# powerblade1430_1v0.net
KiCad netlist of a schematic drawn in EAGLE
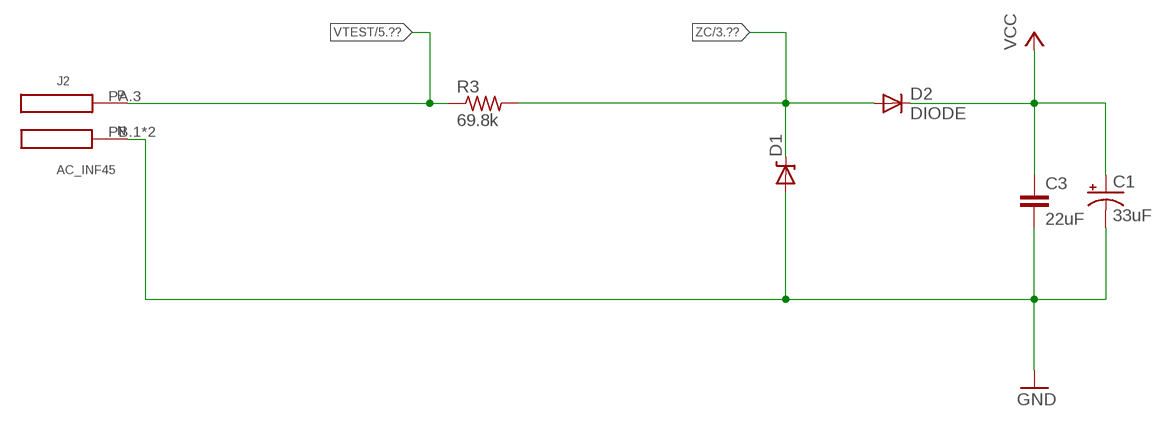
[diagram p0: schematic, sheet 1]
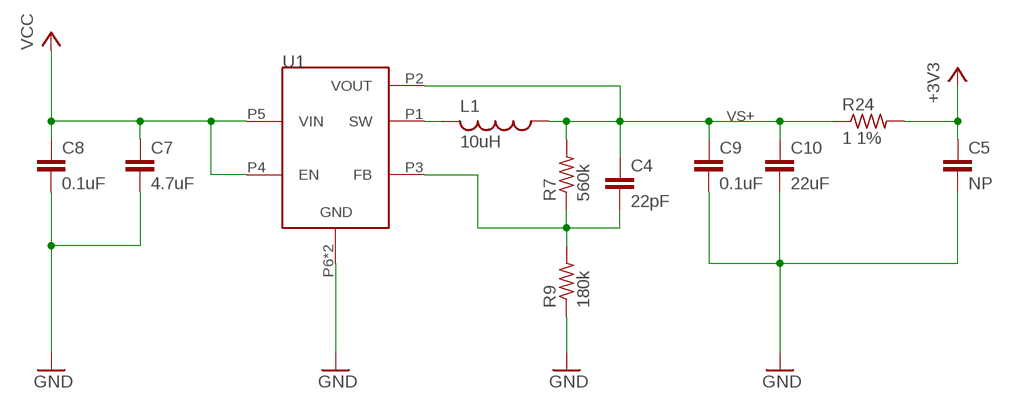
[diagram p1: schematic, sheet 2]
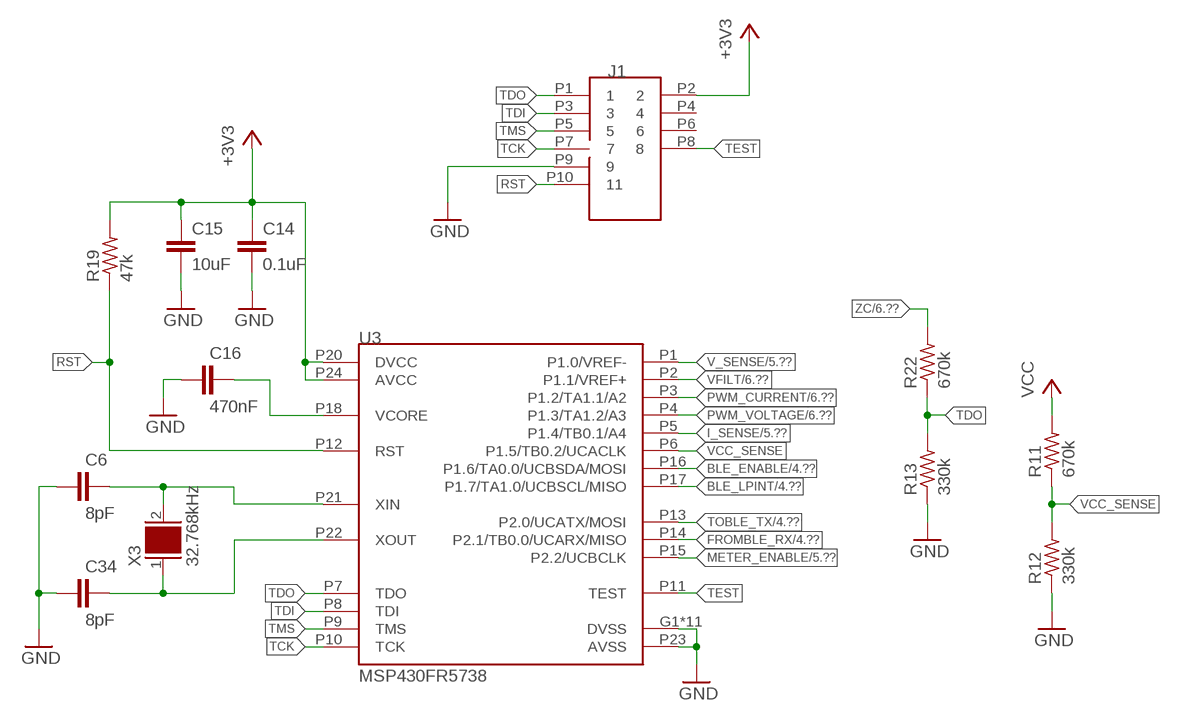
[diagram p2: schematic, sheet 3]
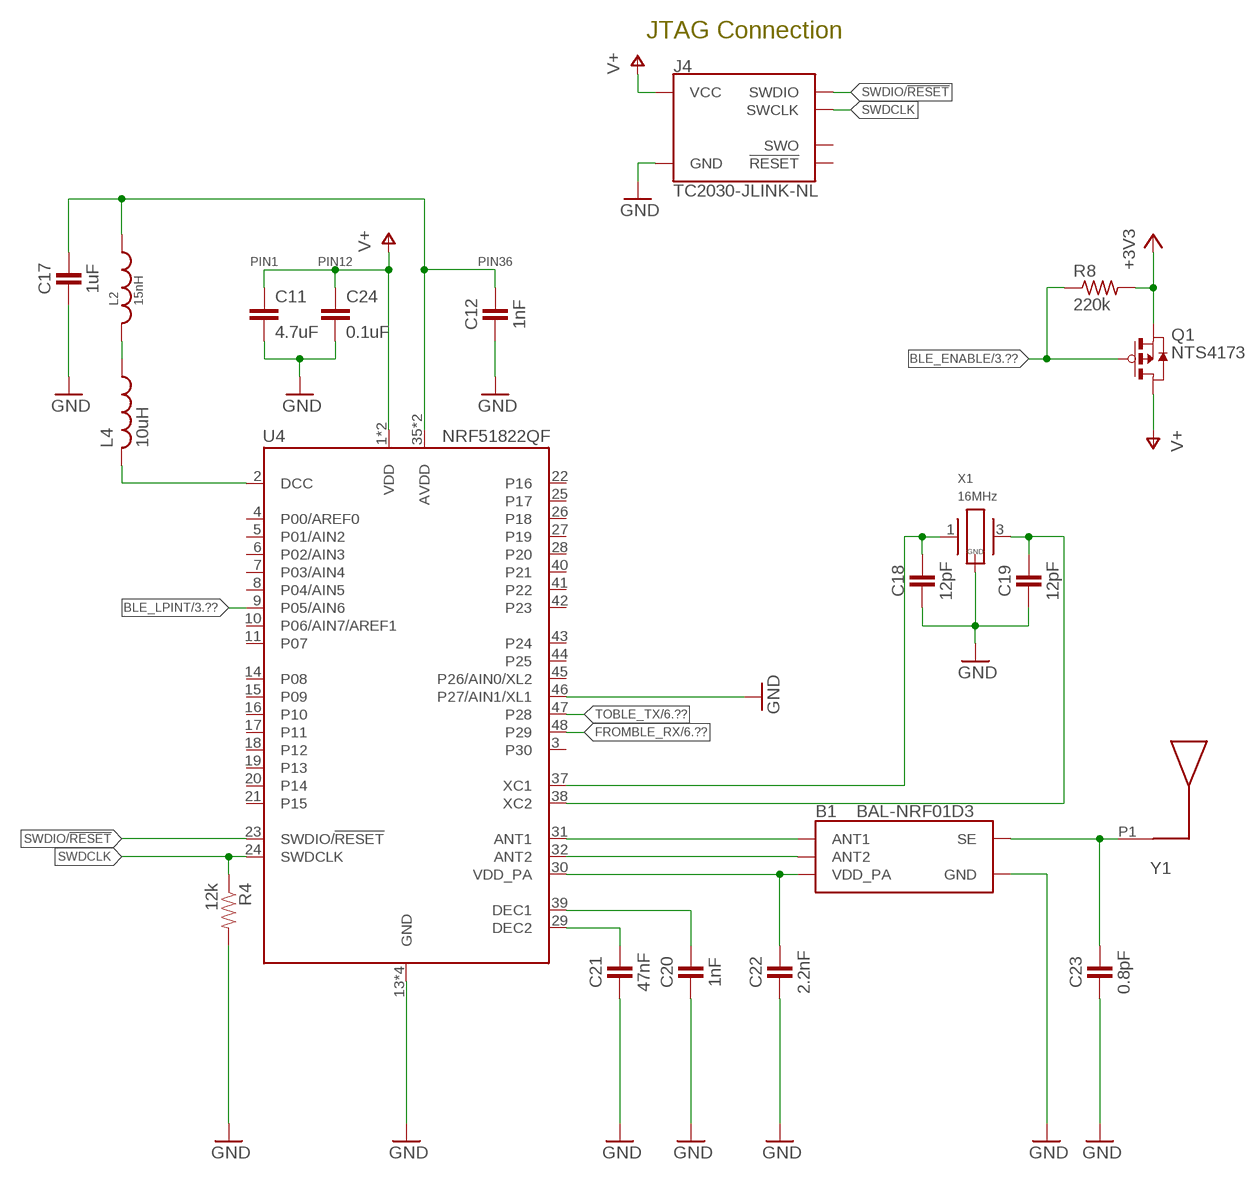
[diagram p3: schematic, sheet 4]
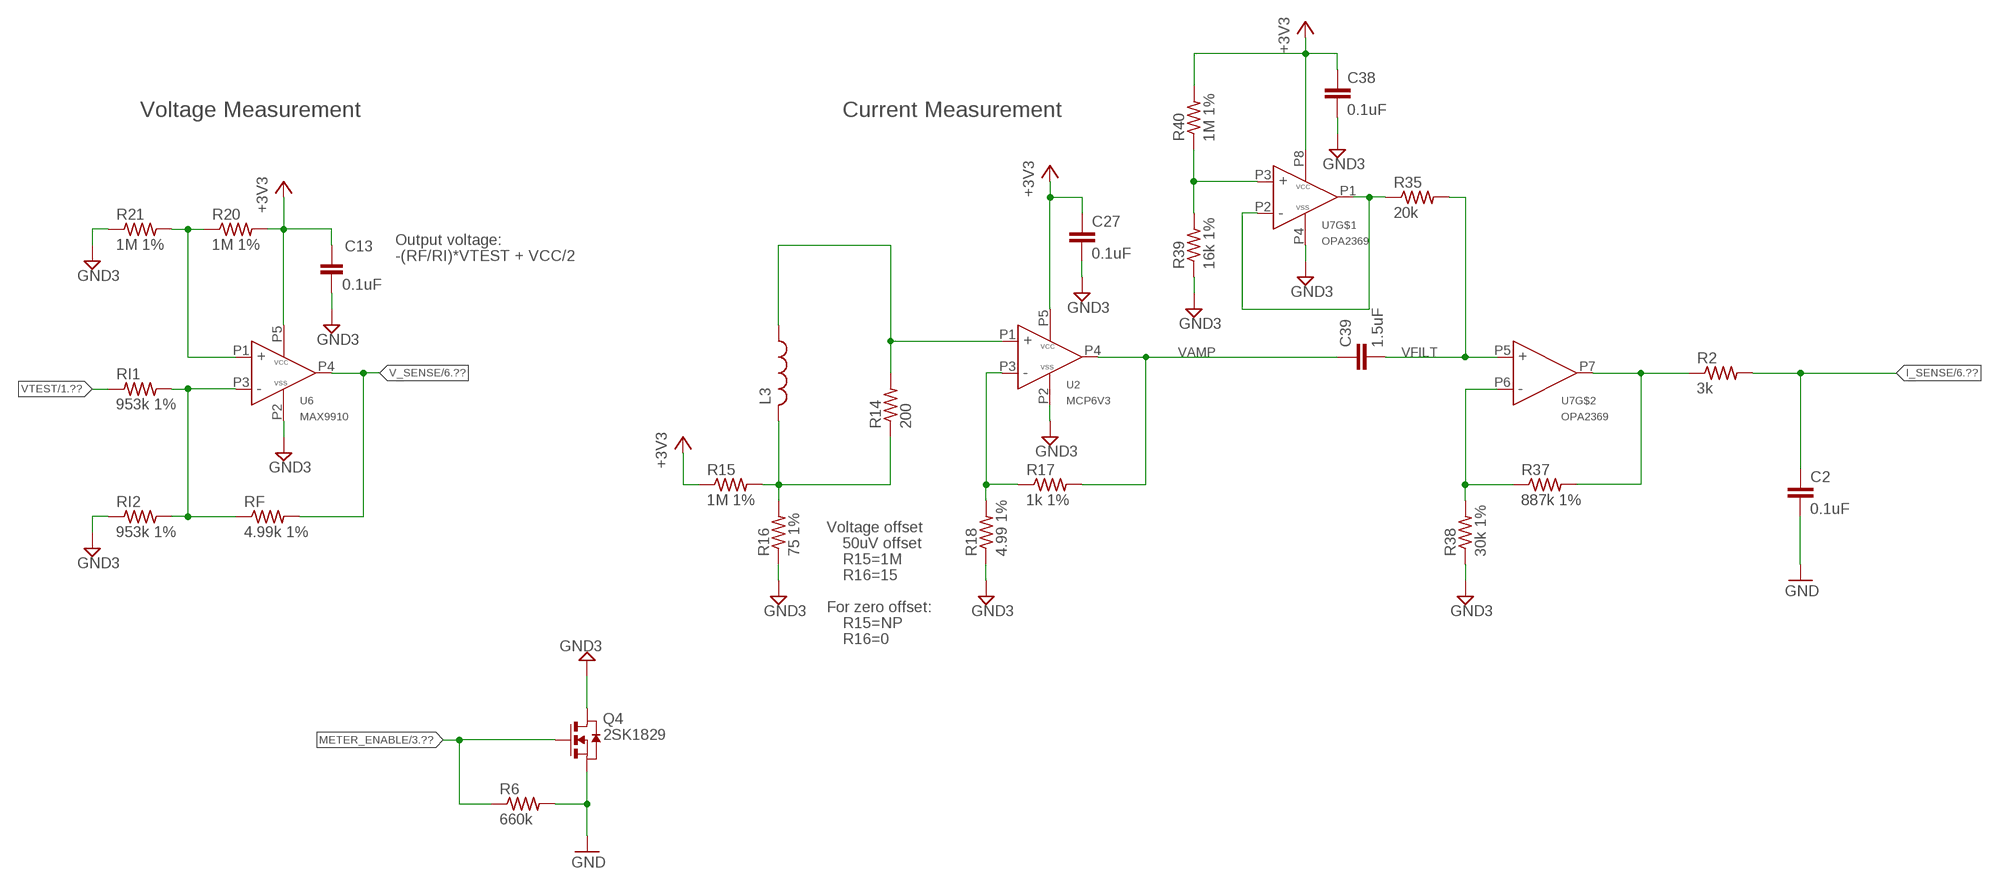
[diagram p4: schematic, sheet 5]
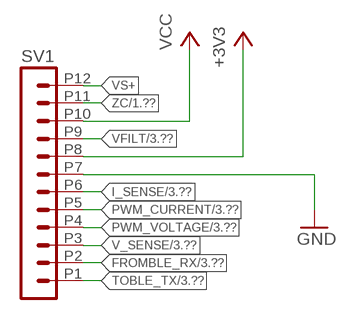
[diagram p5: schematic, sheet 6]

(export (version "E")
  (design (tool "Eeschema 10.0.6"))
  (components
    (comp (ref "SV1")
      (value "MA12-11M27")
      (footprint "eagle-import:MA12-1_1MM27")
      (libsource (lib "eagle-import") (part "MA12-11M27"))
    )
    (comp (ref "B1")
      (value "BAL-NRF01D3")
      (footprint "eagle-import:BAL-NRF01D3")
      (libsource (lib "eagle-import") (part "BAL-NRF01D3"))
    )
    (comp (ref "C11")
      (value "4.7uF")
      (footprint "eagle-import:C0402")
      (libsource (lib "eagle-import") (part "C-EUC0402"))
    )
    (comp (ref "C12")
      (value "1nF")
      (footprint "eagle-import:0402_CAP")
      (libsource (lib "eagle-import") (part "CAPACITOR"))
    )
    (comp (ref "C17")
      (value "1uF")
      (footprint "eagle-import:0402_CAP")
      (libsource (lib "eagle-import") (part "CAPACITOR"))
    )
    (comp (ref "C18")
      (value "12pF")
      (footprint "eagle-import:0402_CAP")
      (libsource (lib "eagle-import") (part "CAPACITOR"))
    )
    (comp (ref "C19")
      (value "12pF")
      (footprint "eagle-import:0402_CAP")
      (libsource (lib "eagle-import") (part "CAPACITOR"))
    )
    (comp (ref "C20")
      (value "1nF")
      (footprint "eagle-import:0402_CAP")
      (libsource (lib "eagle-import") (part "CAPACITOR"))
    )
    (comp (ref "C21")
      (value "47nF")
      (footprint "eagle-import:0402_CAP")
      (libsource (lib "eagle-import") (part "CAPACITOR"))
    )
    (comp (ref "C22")
      (value "2.2nF")
      (footprint "eagle-import:0402_CAP")
      (libsource (lib "eagle-import") (part "CAPACITOR"))
    )
    (comp (ref "C23")
      (value "0.8pF")
      (footprint "eagle-import:0402_CAP")
      (libsource (lib "eagle-import") (part "CAPACITOR"))
    )
    (comp (ref "C24")
      (value "0.1uF")
      (footprint "eagle-import:C0402")
      (libsource (lib "eagle-import") (part "C-EUC0402"))
    )
    (comp (ref "J4")
      (value "TC2030-JLINK-NL")
      (footprint "eagle-import:TC2030-IDC-NL")
      (libsource (lib "eagle-import") (part "TC2030-JLINK-NL"))
    )
    (comp (ref "L2")
      (value "15nH")
      (footprint "eagle-import:0402_CAP")
      (libsource (lib "eagle-import") (part "INDUCTOR0402"))
    )
    (comp (ref "L4")
      (value "10uH")
      (footprint "eagle-import:C0603_TN")
      (libsource (lib "eagle-import") (part "L-USL0603_TN"))
    )
    (comp (ref "Q1")
      (value "NTS4173")
      (footprint "eagle-import:SC-70-3")
      (libsource (lib "eagle-import") (part "NTS4173"))
    )
    (comp (ref "R4")
      (value "12k")
      (footprint "eagle-import:0402_RES")
      (libsource (lib "eagle-import") (part "RESISTOR"))
    )
    (comp (ref "R8")
      (value "220k")
      (footprint "eagle-import:R0402_SM")
      (libsource (lib "eagle-import") (part "R-US_R0402_SM"))
    )
    (comp (ref "U4")
      (value "NRF51822QF")
      (footprint "eagle-import:QFN-48-6MM")
      (libsource (lib "eagle-import") (part "NRF51822QF"))
    )
    (comp (ref "X1")
      (value "16MHz")
      (footprint "eagle-import:TXC-8Y")
      (libsource (lib "eagle-import") (part "TXC-8Y"))
    )
    (comp (ref "Y1")
      (value "UREACH_XTEND")
      (footprint "eagle-import:UREACH_XTEND")
      (libsource (lib "eagle-import") (part "UREACH_XTEND"))
    )
    (comp (ref "C6")
      (value "8pF")
      (footprint "eagle-import:C0402")
      (libsource (lib "eagle-import") (part "C-EUC0402"))
    )
    (comp (ref "C14")
      (value "0.1uF")
      (footprint "eagle-import:C0402")
      (libsource (lib "eagle-import") (part "C-EUC0402"))
    )
    (comp (ref "C15")
      (value "10uF")
      (footprint "eagle-import:C0603_SM")
      (libsource (lib "eagle-import") (part "C-EUC0603_SM"))
    )
    (comp (ref "C16")
      (value "470nF")
      (footprint "eagle-import:C0402")
      (libsource (lib "eagle-import") (part "C-EUC0402"))
    )
    (comp (ref "C34")
      (value "8pF")
      (footprint "eagle-import:C0402")
      (libsource (lib "eagle-import") (part "C-EUC0402"))
    )
    (comp (ref "J1")
      (value "JTAG_14PIN_IDC-ND")
      (footprint "eagle-import:TC2050-IDC-NL-430-ND")
      (libsource (lib "eagle-import") (part "JTAG_14PIN_IDC-ND"))
    )
    (comp (ref "R11")
      (value "670k")
      (footprint "eagle-import:R0402")
      (libsource (lib "eagle-import") (part "R-US_R0402"))
    )
    (comp (ref "R12")
      (value "330k")
      (footprint "eagle-import:R0402")
      (libsource (lib "eagle-import") (part "R-US_R0402"))
    )
    (comp (ref "R13")
      (value "330k")
      (footprint "eagle-import:R0402")
      (libsource (lib "eagle-import") (part "R-US_R0402"))
    )
    (comp (ref "R19")
      (value "47k")
      (footprint "eagle-import:R0402")
      (libsource (lib "eagle-import") (part "R-US_R0402"))
    )
    (comp (ref "R22")
      (value "670k")
      (footprint "eagle-import:R0402")
      (libsource (lib "eagle-import") (part "R-US_R0402"))
    )
    (comp (ref "U3")
      (value "MSP430FR5738")
      (footprint "eagle-import:VQFN-24")
      (libsource (lib "eagle-import") (part "MSP430FR5738"))
    )
    (comp (ref "X3")
      (value "32.768kHz")
      (footprint "eagle-import:0805")
      (libsource (lib "eagle-import") (part "CRYSTAL_0805"))
    )
    (comp (ref "C2")
      (value "0.1uF")
      (footprint "eagle-import:C0402")
      (libsource (lib "eagle-import") (part "C-EUC0402"))
    )
    (comp (ref "C13")
      (value "0.1uF")
      (footprint "eagle-import:0402_CAP")
      (libsource (lib "eagle-import") (part "CAPACITOR"))
    )
    (comp (ref "C27")
      (value "0.1uF")
      (footprint "eagle-import:C0402")
      (libsource (lib "eagle-import") (part "C-EUC0402"))
    )
    (comp (ref "C38")
      (value "0.1uF")
      (footprint "eagle-import:C0402")
      (libsource (lib "eagle-import") (part "C-EUC0402"))
    )
    (comp (ref "C39")
      (value "1.5uF")
      (footprint "eagle-import:C0402")
      (libsource (lib "eagle-import") (part "C-EUC0402"))
    )
    (comp (ref "L3")
      (value "L-USL0805")
      (footprint "eagle-import:L0805")
      (libsource (lib "eagle-import") (part "L-USL0805"))
    )
    (comp (ref "Q4")
      (value "2SK1829")
      (footprint "eagle-import:SC-70-3")
      (libsource (lib "eagle-import") (part "2SK1829"))
    )
    (comp (ref "R2")
      (value "3k")
      (footprint "eagle-import:R0402_SM")
      (libsource (lib "eagle-import") (part "R-US_R0402_SM"))
    )
    (comp (ref "R6")
      (value "660k")
      (footprint "eagle-import:R0402")
      (libsource (lib "eagle-import") (part "R-US_R0402"))
    )
    (comp (ref "R14")
      (value "200")
      (footprint "eagle-import:R0402")
      (libsource (lib "eagle-import") (part "R-US_R0402"))
    )
    (comp (ref "R15")
      (value "1M 1%")
      (footprint "eagle-import:R0402")
      (libsource (lib "eagle-import") (part "R-US_R0402"))
    )
    (comp (ref "R16")
      (value "75 1%")
      (footprint "eagle-import:R0402")
      (libsource (lib "eagle-import") (part "R-US_R0402"))
    )
    (comp (ref "R17")
      (value "1k 1%")
      (footprint "eagle-import:R0402")
      (libsource (lib "eagle-import") (part "R-US_R0402"))
    )
    (comp (ref "R18")
      (value "4.99 1%")
      (footprint "eagle-import:R0402")
      (libsource (lib "eagle-import") (part "R-US_R0402"))
    )
    (comp (ref "R20")
      (value "1M 1%")
      (footprint "eagle-import:R0402")
      (libsource (lib "eagle-import") (part "R-US_R0402"))
    )
    (comp (ref "R21")
      (value "1M 1%")
      (footprint "eagle-import:R0402_SM")
      (libsource (lib "eagle-import") (part "R-US_R0402_SM"))
    )
    (comp (ref "R35")
      (value "20k")
      (footprint "eagle-import:R0402")
      (libsource (lib "eagle-import") (part "R-US_R0402"))
    )
    (comp (ref "R37")
      (value "887k 1%")
      (footprint "eagle-import:R0402")
      (libsource (lib "eagle-import") (part "R-US_R0402"))
    )
    (comp (ref "R38")
      (value "30k 1%")
      (footprint "eagle-import:R0402")
      (libsource (lib "eagle-import") (part "R-US_R0402"))
    )
    (comp (ref "R39")
      (value "16k 1%")
      (footprint "eagle-import:R0402")
      (libsource (lib "eagle-import") (part "R-US_R0402"))
    )
    (comp (ref "R40")
      (value "1M 1%")
      (footprint "eagle-import:R0402")
      (libsource (lib "eagle-import") (part "R-US_R0402"))
    )
    (comp (ref "RF")
      (value "4.99k 1%")
      (footprint "eagle-import:R0402")
      (libsource (lib "eagle-import") (part "R-US_R0402"))
    )
    (comp (ref "RI1")
      (value "953k 1%")
      (footprint "eagle-import:R0402")
      (libsource (lib "eagle-import") (part "R-US_R0402"))
    )
    (comp (ref "RI2")
      (value "953k 1%")
      (footprint "eagle-import:R0402")
      (libsource (lib "eagle-import") (part "R-US_R0402"))
    )
    (comp (ref "U2")
      (value "MCP6V3")
      (footprint "eagle-import:SC70-5")
      (fields (field (name "DIGIKEY") "296-19547-1-ND"))
      (libsource (lib "eagle-import") (part "MCP6V3"))
    )
    (comp (ref "U6")
      (value "MAX9910")
      (footprint "eagle-import:SC70-5")
      (fields (field (name "DIGIKEY") "296-25252-1-ND"))
      (libsource (lib "eagle-import") (part "MAX9910"))
    )
    (comp (ref "U7")
      (value "OPA2369")
      (footprint "eagle-import:SOT-23-8")
      (libsource (lib "eagle-import") (part "OPA2369"))
    )
    (comp (ref "C4")
      (value "22pF")
      (footprint "eagle-import:C0402")
      (libsource (lib "eagle-import") (part "C-EUC0402"))
    )
    (comp (ref "C5")
      (value "NP")
      (footprint "eagle-import:C0603_TN")
      (libsource (lib "eagle-import") (part "C-EUC0603_TN"))
    )
    (comp (ref "C7")
      (value "4.7uF")
      (footprint "eagle-import:C0402")
      (libsource (lib "eagle-import") (part "C-EUC0402"))
    )
    (comp (ref "C8")
      (value "0.1uF")
      (footprint "eagle-import:C0402")
      (libsource (lib "eagle-import") (part "C-EUC0402"))
    )
    (comp (ref "C9")
      (value "0.1uF")
      (footprint "eagle-import:C0402_SM")
      (libsource (lib "eagle-import") (part "C-EUC0402_SM"))
    )
    (comp (ref "C10")
      (value "22uF")
      (footprint "eagle-import:C0603_SM")
      (libsource (lib "eagle-import") (part "C-EUC0603_SM"))
    )
    (comp (ref "L1")
      (value "10uH")
      (footprint "eagle-import:L0805")
      (libsource (lib "eagle-import") (part "L-USL0805"))
    )
    (comp (ref "R7")
      (value "560k")
      (footprint "eagle-import:R0402")
      (libsource (lib "eagle-import") (part "R-US_R0402"))
    )
    (comp (ref "R9")
      (value "180k")
      (footprint "eagle-import:R0402")
      (libsource (lib "eagle-import") (part "R-US_R0402"))
    )
    (comp (ref "R24")
      (value "1 1%")
      (footprint "eagle-import:R0603_SM")
      (libsource (lib "eagle-import") (part "R-US_R0603_SM"))
    )
    (comp (ref "U1")
      (value "TPS62122")
      (footprint "eagle-import:WDFN-6")
      (libsource (lib "eagle-import") (part "TPS62122"))
    )
    (comp (ref "C1")
      (value "33uF")
      (footprint "eagle-import:CPOL0805_SM")
      (libsource (lib "eagle-import") (part "CPOL-US0805_SM"))
    )
    (comp (ref "C3")
      (value "22uF")
      (footprint "eagle-import:C0603_SM")
      (libsource (lib "eagle-import") (part "C-EUC0603_SM"))
    )
    (comp (ref "D1")
      (value "ZENERBZT52")
      (footprint "eagle-import:BZT52")
      (fields (field (name "DIGIKEY") "BZT52C10T-7DICT-ND "))
      (libsource (lib "eagle-import") (part "ZENERBZT52"))
    )
    (comp (ref "D2")
      (value "DIODE")
      (footprint "eagle-import:BAS521")
      (libsource (lib "eagle-import") (part "DIODE"))
    )
    (comp (ref "J2")
      (value "AC_INF45")
      (footprint "eagle-import:AC3_F45")
      (libsource (lib "eagle-import") (part "AC_INF45"))
    )
    (comp (ref "R3")
      (value "69.8k")
      (footprint "eagle-import:R1210")
      (libsource (lib "eagle-import") (part "R-US_R1210"))
    )
  )
  (nets
    (net (code "1") (name "+3V3") (class "Default")
      (node (ref "C13") (pin "1") (pinfunction "1_1") (pintype "bidirectional"))
      (node (ref "C14") (pin "1") (pinfunction "1_1") (pintype "passive"))
      (node (ref "C15") (pin "1") (pinfunction "1_1") (pintype "passive"))
      (node (ref "C27") (pin "1") (pinfunction "1_1") (pintype "passive"))
      (node (ref "C38") (pin "1") (pinfunction "1_1") (pintype "passive"))
      (node (ref "C5") (pin "1") (pinfunction "1_1") (pintype "passive"))
      (node (ref "J1") (pin "P2") (pinfunction "2_P2") (pintype "bidirectional"))
      (node (ref "Q1") (pin "P2") (pinfunction "S_P2") (pintype "passive"))
      (node (ref "R15") (pin "1") (pinfunction "1_1") (pintype "passive"))
      (node (ref "R19") (pin "2") (pinfunction "2_2") (pintype "passive"))
      (node (ref "R20") (pin "2") (pinfunction "2_2") (pintype "passive"))
      (node (ref "R24") (pin "2") (pinfunction "2_2") (pintype "passive"))
      (node (ref "R40") (pin "2") (pinfunction "2_2") (pintype "passive"))
      (node (ref "R8") (pin "2") (pinfunction "2_2") (pintype "passive"))
      (node (ref "SV1") (pin "P8") (pinfunction "8_P8") (pintype "passive"))
      (node (ref "U2") (pin "P5") (pinfunction "VCC_P5") (pintype "bidirectional"))
      (node (ref "U3") (pin "P20") (pinfunction "DVCC_P20") (pintype "bidirectional"))
      (node (ref "U3") (pin "P24") (pinfunction "AVCC_P24") (pintype "bidirectional"))
      (node (ref "U6") (pin "P5") (pinfunction "VCC_P5") (pintype "bidirectional"))
      (node (ref "U7") (pin "P8") (pinfunction "VCC_P8") (pintype "bidirectional"))
    )
    (net (code "2") (name "BLE_ENABLE") (class "Default")
      (node (ref "Q1") (pin "P1") (pinfunction "G_P1") (pintype "passive"))
      (node (ref "R8") (pin "1") (pinfunction "1_1") (pintype "passive"))
      (node (ref "U3") (pin "P16") (pinfunction "P1.6/TA0.0/UCBSDA/MOSI_P16") (pintype "bidirectional"))
    )
    (net (code "3") (name "BLE_LPINT") (class "Default")
      (node (ref "U3") (pin "P17") (pinfunction "P1.7/TA1.0/UCBSCL/MISO_P17") (pintype "bidirectional"))
      (node (ref "U4") (pin "9") (pinfunction "P05/AIN6_9") (pintype "bidirectional"))
    )
    (net (code "4") (name "FROMBLE_RX") (class "Default")
      (node (ref "SV1") (pin "P2") (pinfunction "2_P2") (pintype "passive"))
      (node (ref "U3") (pin "P14") (pinfunction "P2.1/TB0.0/UCARX/MISO_P14") (pintype "bidirectional"))
      (node (ref "U4") (pin "48") (pinfunction "P29_48") (pintype "bidirectional"))
    )
    (net (code "5") (name "GND") (class "Default")
      (node (ref "B1") (pin "GND") (pinfunction "GND_GND") (pintype "bidirectional"))
      (node (ref "C1") (pin "-") (pinfunction "-_-") (pintype "passive"))
      (node (ref "C10") (pin "2") (pinfunction "2_2") (pintype "passive"))
      (node (ref "C11") (pin "2") (pinfunction "2_2") (pintype "passive"))
      (node (ref "C12") (pin "2") (pinfunction "2_2") (pintype "bidirectional"))
      (node (ref "C14") (pin "2") (pinfunction "2_2") (pintype "passive"))
      (node (ref "C15") (pin "2") (pinfunction "2_2") (pintype "passive"))
      (node (ref "C16") (pin "1") (pinfunction "1_1") (pintype "passive"))
      (node (ref "C17") (pin "2") (pinfunction "2_2") (pintype "bidirectional"))
      (node (ref "C18") (pin "2") (pinfunction "2_2") (pintype "bidirectional"))
      (node (ref "C19") (pin "2") (pinfunction "2_2") (pintype "bidirectional"))
      (node (ref "C2") (pin "2") (pinfunction "2_2") (pintype "passive"))
      (node (ref "C20") (pin "2") (pinfunction "2_2") (pintype "bidirectional"))
      (node (ref "C21") (pin "2") (pinfunction "2_2") (pintype "bidirectional"))
      (node (ref "C22") (pin "2") (pinfunction "2_2") (pintype "bidirectional"))
      (node (ref "C23") (pin "2") (pinfunction "2_2") (pintype "bidirectional"))
      (node (ref "C24") (pin "2") (pinfunction "2_2") (pintype "passive"))
      (node (ref "C3") (pin "2") (pinfunction "2_2") (pintype "passive"))
      (node (ref "C34") (pin "1") (pinfunction "1_1") (pintype "passive"))
      (node (ref "C5") (pin "2") (pinfunction "2_2") (pintype "passive"))
      (node (ref "C6") (pin "1") (pinfunction "1_1") (pintype "passive"))
      (node (ref "C7") (pin "2") (pinfunction "2_2") (pintype "passive"))
      (node (ref "C8") (pin "2") (pinfunction "2_2") (pintype "passive"))
      (node (ref "C9") (pin "2") (pinfunction "2_2") (pintype "passive"))
      (node (ref "D1") (pin "A") (pinfunction "A_A") (pintype "passive"))
      (node (ref "J1") (pin "P9") (pinfunction "9_P9") (pintype "bidirectional"))
      (node (ref "J2") (pin "PB.1") (pinfunction "N_PB.1") (pintype "bidirectional"))
      (node (ref "J2") (pin "PB.3") (pinfunction "N_PB.3") (pintype "bidirectional"))
      (node (ref "J4") (pin "5") (pinfunction "GND_5") (pintype "bidirectional"))
      (node (ref "Q4") (pin "P2") (pinfunction "S_P2") (pintype "passive"))
      (node (ref "R12") (pin "1") (pinfunction "1_1") (pintype "passive"))
      (node (ref "R13") (pin "1") (pinfunction "1_1") (pintype "passive"))
      (node (ref "R4") (pin "2") (pinfunction "2_2") (pintype "passive"))
      (node (ref "R6") (pin "2") (pinfunction "2_2") (pintype "passive"))
      (node (ref "R9") (pin "1") (pinfunction "1_1") (pintype "passive"))
      (node (ref "SV1") (pin "P7") (pinfunction "7_P7") (pintype "passive"))
      (node (ref "U1") (pin "P6") (pinfunction "GND_P6") (pintype "bidirectional"))
      (node (ref "U1") (pin "PAD") (pinfunction "GND_PAD") (pintype "bidirectional"))
      (node (ref "U3") (pin "G1") (pinfunction "DVSS_G1") (pintype "bidirectional"))
      (node (ref "U3") (pin "G2") (pinfunction "DVSS_G2") (pintype "bidirectional"))
      (node (ref "U3") (pin "G3") (pinfunction "DVSS_G3") (pintype "bidirectional"))
      (node (ref "U3") (pin "G4") (pinfunction "DVSS_G4") (pintype "bidirectional"))
      (node (ref "U3") (pin "G5") (pinfunction "DVSS_G5") (pintype "bidirectional"))
      (node (ref "U3") (pin "G6") (pinfunction "DVSS_G6") (pintype "bidirectional"))
      (node (ref "U3") (pin "G7") (pinfunction "DVSS_G7") (pintype "bidirectional"))
      (node (ref "U3") (pin "G8") (pinfunction "DVSS_G8") (pintype "bidirectional"))
      (node (ref "U3") (pin "G9") (pinfunction "DVSS_G9") (pintype "bidirectional"))
      (node (ref "U3") (pin "P19") (pinfunction "DVSS_P19") (pintype "bidirectional"))
      (node (ref "U3") (pin "P23") (pinfunction "AVSS_P23") (pintype "bidirectional"))
      (node (ref "U3") (pin "PAD") (pinfunction "DVSS_PAD") (pintype "bidirectional"))
      (node (ref "U4") (pin "13") (pinfunction "GND_13") (pintype "bidirectional"))
      (node (ref "U4") (pin "33") (pinfunction "GND_33") (pintype "bidirectional"))
      (node (ref "U4") (pin "34") (pinfunction "GND_34") (pintype "bidirectional"))
      (node (ref "U4") (pin "46") (pinfunction "P27/AIN1/XL1_46") (pintype "bidirectional"))
      (node (ref "U4") (pin "GND") (pinfunction "GND_GND") (pintype "bidirectional"))
      (node (ref "X1") (pin "2") (pinfunction "GND_2") (pintype "bidirectional"))
      (node (ref "X1") (pin "4") (pinfunction "GND_4") (pintype "bidirectional"))
    )
    (net (code "6") (name "GND3") (class "Default")
      (node (ref "C13") (pin "2") (pinfunction "2_2") (pintype "bidirectional"))
      (node (ref "C27") (pin "2") (pinfunction "2_2") (pintype "passive"))
      (node (ref "C38") (pin "2") (pinfunction "2_2") (pintype "passive"))
      (node (ref "Q4") (pin "P3") (pinfunction "D_P3") (pintype "passive"))
      (node (ref "R16") (pin "1") (pinfunction "1_1") (pintype "passive"))
      (node (ref "R18") (pin "1") (pinfunction "1_1") (pintype "passive"))
      (node (ref "R21") (pin "1") (pinfunction "1_1") (pintype "passive"))
      (node (ref "R38") (pin "1") (pinfunction "1_1") (pintype "passive"))
      (node (ref "R39") (pin "1") (pinfunction "1_1") (pintype "passive"))
      (node (ref "RI2") (pin "1") (pinfunction "1_1") (pintype "passive"))
      (node (ref "U2") (pin "P2") (pinfunction "VSS_P2") (pintype "bidirectional"))
      (node (ref "U6") (pin "P2") (pinfunction "VSS_P2") (pintype "bidirectional"))
      (node (ref "U7") (pin "P4") (pinfunction "VSS_P4") (pintype "bidirectional"))
    )
    (net (code "7") (name "I_SENSE") (class "Default")
      (node (ref "C2") (pin "1") (pinfunction "1_1") (pintype "passive"))
      (node (ref "R2") (pin "2") (pinfunction "2_2") (pintype "passive"))
      (node (ref "SV1") (pin "P6") (pinfunction "6_P6") (pintype "passive"))
      (node (ref "U3") (pin "P5") (pinfunction "P1.4/TB0.1/A4_P5") (pintype "bidirectional"))
    )
    (net (code "8") (name "METER_ENABLE") (class "Default")
      (node (ref "Q4") (pin "P1") (pinfunction "G_P1") (pintype "passive"))
      (node (ref "R6") (pin "1") (pinfunction "1_1") (pintype "passive"))
      (node (ref "U3") (pin "P15") (pinfunction "P2.2/UCBCLK_P15") (pintype "bidirectional"))
    )
    (net (code "9") (name "Net-(B1-PadSE)") (class "Default")
      (node (ref "B1") (pin "SE") (pinfunction "SE_SE") (pintype "bidirectional"))
      (node (ref "C23") (pin "1") (pinfunction "1_1") (pintype "bidirectional"))
      (node (ref "Y1") (pin "P1") (pinfunction "P1_P1") (pintype "bidirectional"))
    )
    (net (code "10") (name "Net-(B1-VDD_PA)") (class "Default")
      (node (ref "B1") (pin "VCC") (pinfunction "VDD_PA_VCC") (pintype "bidirectional"))
      (node (ref "C22") (pin "1") (pinfunction "1_1") (pintype "bidirectional"))
      (node (ref "U4") (pin "30") (pinfunction "VDD_PA_30") (pintype "bidirectional"))
    )
    (net (code "11") (name "Net-(C12-Pad1)") (class "Default")
      (node (ref "C12") (pin "1") (pinfunction "1_1") (pintype "bidirectional"))
      (node (ref "C17") (pin "1") (pinfunction "1_1") (pintype "bidirectional"))
      (node (ref "L2") (pin "1") (pinfunction "1_1") (pintype "bidirectional"))
      (node (ref "U4") (pin "35") (pinfunction "AVDD_35") (pintype "bidirectional"))
      (node (ref "U4") (pin "36") (pinfunction "AVDD_36") (pintype "bidirectional"))
    )
    (net (code "12") (name "Net-(L2-Pad2)") (class "Default")
      (node (ref "L2") (pin "2") (pinfunction "2_2") (pintype "bidirectional"))
      (node (ref "L4") (pin "1") (pinfunction "1_1") (pintype "passive"))
    )
    (net (code "13") (name "Net-(L3-Pad2)") (class "Default")
      (node (ref "L3") (pin "2") (pinfunction "2_2") (pintype "passive"))
      (node (ref "R14") (pin "1") (pinfunction "1_1") (pintype "passive"))
      (node (ref "R15") (pin "2") (pinfunction "2_2") (pintype "passive"))
      (node (ref "R16") (pin "2") (pinfunction "2_2") (pintype "passive"))
    )
    (net (code "14") (name "Net-(U1-FB)") (class "Default")
      (node (ref "C4") (pin "2") (pinfunction "2_2") (pintype "passive"))
      (node (ref "R7") (pin "1") (pinfunction "1_1") (pintype "passive"))
      (node (ref "R9") (pin "2") (pinfunction "2_2") (pintype "passive"))
      (node (ref "U1") (pin "P3") (pinfunction "FB_P3") (pintype "bidirectional"))
    )
    (net (code "15") (name "Net-(U1-SW)") (class "Default")
      (node (ref "L1") (pin "2") (pinfunction "2_2") (pintype "passive"))
      (node (ref "U1") (pin "P1") (pinfunction "SW_P1") (pintype "bidirectional"))
    )
    (net (code "16") (name "Net-(U2-IN+)") (class "Default")
      (node (ref "L3") (pin "1") (pinfunction "1_1") (pintype "passive"))
      (node (ref "R14") (pin "2") (pinfunction "2_2") (pintype "passive"))
      (node (ref "U2") (pin "P1") (pinfunction "IN+_P1") (pintype "bidirectional"))
    )
    (net (code "17") (name "Net-(U2-IN-)") (class "Default")
      (node (ref "R17") (pin "1") (pinfunction "1_1") (pintype "passive"))
      (node (ref "R18") (pin "2") (pinfunction "2_2") (pintype "passive"))
      (node (ref "U2") (pin "P3") (pinfunction "IN-_P3") (pintype "bidirectional"))
    )
    (net (code "18") (name "Net-(U3-VCORE)") (class "Default")
      (node (ref "C16") (pin "2") (pinfunction "2_2") (pintype "passive"))
      (node (ref "U3") (pin "P18") (pinfunction "VCORE_P18") (pintype "bidirectional"))
    )
    (net (code "19") (name "Net-(U3-XIN)") (class "Default")
      (node (ref "C6") (pin "2") (pinfunction "2_2") (pintype "passive"))
      (node (ref "U3") (pin "P21") (pinfunction "XIN_P21") (pintype "bidirectional"))
      (node (ref "X3") (pin "2") (pinfunction "P2_2") (pintype "bidirectional"))
    )
    (net (code "20") (name "Net-(U3-XOUT)") (class "Default")
      (node (ref "C34") (pin "2") (pinfunction "2_2") (pintype "passive"))
      (node (ref "U3") (pin "P22") (pinfunction "XOUT_P22") (pintype "bidirectional"))
      (node (ref "X3") (pin "1") (pinfunction "P1_1") (pintype "bidirectional"))
    )
    (net (code "21") (name "Net-(U4-ANT1)") (class "Default")
      (node (ref "B1") (pin "ANT1") (pinfunction "ANT1_ANT1") (pintype "bidirectional"))
      (node (ref "U4") (pin "31") (pinfunction "ANT1_31") (pintype "bidirectional"))
    )
    (net (code "22") (name "Net-(U4-ANT2)") (class "Default")
      (node (ref "B1") (pin "ANT2") (pinfunction "ANT2_ANT2") (pintype "bidirectional"))
      (node (ref "U4") (pin "32") (pinfunction "ANT2_32") (pintype "bidirectional"))
    )
    (net (code "23") (name "Net-(U4-DCC)") (class "Default")
      (node (ref "L4") (pin "2") (pinfunction "2_2") (pintype "passive"))
      (node (ref "U4") (pin "2") (pinfunction "DCC_2") (pintype "bidirectional"))
    )
    (net (code "24") (name "Net-(U4-DEC1)") (class "Default")
      (node (ref "C20") (pin "1") (pinfunction "1_1") (pintype "bidirectional"))
      (node (ref "U4") (pin "39") (pinfunction "DEC1_39") (pintype "bidirectional"))
    )
    (net (code "25") (name "Net-(U4-DEC2)") (class "Default")
      (node (ref "C21") (pin "1") (pinfunction "1_1") (pintype "bidirectional"))
      (node (ref "U4") (pin "29") (pinfunction "DEC2_29") (pintype "bidirectional"))
    )
    (net (code "26") (name "Net-(U4-XC1)") (class "Default")
      (node (ref "C18") (pin "1") (pinfunction "1_1") (pintype "bidirectional"))
      (node (ref "U4") (pin "37") (pinfunction "XC1_37") (pintype "bidirectional"))
      (node (ref "X1") (pin "1") (pinfunction "1_1") (pintype "bidirectional"))
    )
    (net (code "27") (name "Net-(U4-XC2)") (class "Default")
      (node (ref "C19") (pin "1") (pinfunction "1_1") (pintype "bidirectional"))
      (node (ref "U4") (pin "38") (pinfunction "XC2_38") (pintype "bidirectional"))
      (node (ref "X1") (pin "3") (pinfunction "2_3") (pintype "bidirectional"))
    )
    (net (code "28") (name "Net-(U6-IN+)") (class "Default")
      (node (ref "R20") (pin "1") (pinfunction "1_1") (pintype "passive"))
      (node (ref "R21") (pin "2") (pinfunction "2_2") (pintype "passive"))
      (node (ref "U6") (pin "P1") (pinfunction "IN+_P1") (pintype "bidirectional"))
    )
    (net (code "29") (name "Net-(U6-IN-)") (class "Default")
      (node (ref "RF") (pin "1") (pinfunction "1_1") (pintype "passive"))
      (node (ref "RI1") (pin "2") (pinfunction "2_2") (pintype "passive"))
      (node (ref "RI2") (pin "2") (pinfunction "2_2") (pintype "passive"))
      (node (ref "U6") (pin "P3") (pinfunction "IN-_P3") (pintype "bidirectional"))
    )
    (net (code "30") (name "Net-(U7A-IN+)") (class "Default")
      (node (ref "R39") (pin "2") (pinfunction "2_2") (pintype "passive"))
      (node (ref "R40") (pin "1") (pinfunction "1_1") (pintype "passive"))
      (node (ref "U7") (pin "P3") (pinfunction "IN+_P3") (pintype "bidirectional"))
    )
    (net (code "31") (name "Net-(U7A-IN-)") (class "Default")
      (node (ref "R35") (pin "1") (pinfunction "1_1") (pintype "passive"))
      (node (ref "U7") (pin "P1") (pinfunction "OUT_P1") (pintype "bidirectional"))
      (node (ref "U7") (pin "P2") (pinfunction "IN-_P2") (pintype "bidirectional"))
    )
    (net (code "32") (name "Net-(U7B-IN-)") (class "Default")
      (node (ref "R37") (pin "1") (pinfunction "1_1") (pintype "passive"))
      (node (ref "R38") (pin "2") (pinfunction "2_2") (pintype "passive"))
      (node (ref "U7") (pin "P6") (pinfunction "IN-_P6") (pintype "bidirectional"))
    )
    (net (code "33") (name "Net-(U7B-OUT)") (class "Default")
      (node (ref "R2") (pin "1") (pinfunction "1_1") (pintype "passive"))
      (node (ref "R37") (pin "2") (pinfunction "2_2") (pintype "passive"))
      (node (ref "U7") (pin "P7") (pinfunction "OUT_P7") (pintype "bidirectional"))
    )
    (net (code "34") (name "PWM_CURRENT") (class "Default")
      (node (ref "SV1") (pin "P5") (pinfunction "5_P5") (pintype "passive"))
      (node (ref "U3") (pin "P3") (pinfunction "P1.2/TA1.1/A2_P3") (pintype "bidirectional"))
    )
    (net (code "35") (name "PWM_VOLTAGE") (class "Default")
      (node (ref "SV1") (pin "P4") (pinfunction "4_P4") (pintype "passive"))
      (node (ref "U3") (pin "P4") (pinfunction "P1.3/TA1.2/A3_P4") (pintype "bidirectional"))
    )
    (net (code "36") (name "RST") (class "Default")
      (node (ref "J1") (pin "P10") (pinfunction "11_P10") (pintype "bidirectional"))
      (node (ref "R19") (pin "1") (pinfunction "1_1") (pintype "passive"))
      (node (ref "U3") (pin "P12") (pinfunction "RST_P12") (pintype "bidirectional"))
    )
    (net (code "37") (name "SWDCLK") (class "Default")
      (node (ref "J4") (pin "4") (pinfunction "SWCLK_4") (pintype "bidirectional"))
      (node (ref "R4") (pin "1") (pinfunction "1_1") (pintype "passive"))
      (node (ref "U4") (pin "24") (pinfunction "SWDCLK_24") (pintype "bidirectional"))
    )
    (net (code "38") (name "SWDIO{slash}~{RESET}") (class "Default")
      (node (ref "J4") (pin "2") (pinfunction "SWDIO_2") (pintype "bidirectional"))
      (node (ref "U4") (pin "23") (pinfunction "SWDIO/~{RESET}_23") (pintype "bidirectional"))
    )
    (net (code "39") (name "TCK") (class "Default")
      (node (ref "J1") (pin "P7") (pinfunction "7_P7") (pintype "bidirectional"))
      (node (ref "U3") (pin "P10") (pinfunction "TCK_P10") (pintype "bidirectional"))
    )
    (net (code "40") (name "TDI") (class "Default")
      (node (ref "J1") (pin "P3") (pinfunction "3_P3") (pintype "bidirectional"))
      (node (ref "U3") (pin "P8") (pinfunction "TDI_P8") (pintype "bidirectional"))
    )
    (net (code "41") (name "TDO") (class "Default")
      (node (ref "J1") (pin "P1") (pinfunction "1_P1") (pintype "bidirectional"))
      (node (ref "R13") (pin "2") (pinfunction "2_2") (pintype "passive"))
      (node (ref "R22") (pin "1") (pinfunction "1_1") (pintype "passive"))
      (node (ref "U3") (pin "P7") (pinfunction "TDO_P7") (pintype "bidirectional"))
    )
    (net (code "42") (name "TEST") (class "Default")
      (node (ref "J1") (pin "P8") (pinfunction "8_P8") (pintype "bidirectional"))
      (node (ref "U3") (pin "P11") (pinfunction "TEST_P11") (pintype "bidirectional"))
    )
    (net (code "43") (name "TMS") (class "Default")
      (node (ref "J1") (pin "P5") (pinfunction "5_P5") (pintype "bidirectional"))
      (node (ref "U3") (pin "P9") (pinfunction "TMS_P9") (pintype "bidirectional"))
    )
    (net (code "44") (name "TOBLE_TX") (class "Default")
      (node (ref "SV1") (pin "P1") (pinfunction "1_P1") (pintype "passive"))
      (node (ref "U3") (pin "P13") (pinfunction "P2.0/UCATX/MOSI_P13") (pintype "bidirectional"))
      (node (ref "U4") (pin "47") (pinfunction "P28_47") (pintype "bidirectional"))
    )
    (net (code "45") (name "V+") (class "Default")
      (node (ref "C11") (pin "1") (pinfunction "1_1") (pintype "passive"))
      (node (ref "C24") (pin "1") (pinfunction "1_1") (pintype "passive"))
      (node (ref "J4") (pin "1") (pinfunction "VCC_1") (pintype "bidirectional"))
      (node (ref "Q1") (pin "P3") (pinfunction "D_P3") (pintype "passive"))
      (node (ref "U4") (pin "1") (pinfunction "VDD_1") (pintype "bidirectional"))
      (node (ref "U4") (pin "12") (pinfunction "VDD_12") (pintype "bidirectional"))
    )
    (net (code "46") (name "VAMP") (class "Default")
      (node (ref "C39") (pin "1") (pinfunction "1_1") (pintype "passive"))
      (node (ref "R17") (pin "2") (pinfunction "2_2") (pintype "passive"))
      (node (ref "U2") (pin "P4") (pinfunction "OUT_P4") (pintype "bidirectional"))
    )
    (net (code "47") (name "VCC") (class "Default")
      (node (ref "C1") (pin "+") (pinfunction "+_+") (pintype "passive"))
      (node (ref "C3") (pin "1") (pinfunction "1_1") (pintype "passive"))
      (node (ref "C7") (pin "1") (pinfunction "1_1") (pintype "passive"))
      (node (ref "C8") (pin "1") (pinfunction "1_1") (pintype "passive"))
      (node (ref "D2") (pin "C") (pinfunction "C_C") (pintype "passive"))
      (node (ref "R11") (pin "2") (pinfunction "2_2") (pintype "passive"))
      (node (ref "SV1") (pin "P10") (pinfunction "10_P10") (pintype "passive"))
      (node (ref "U1") (pin "P4") (pinfunction "EN_P4") (pintype "bidirectional"))
      (node (ref "U1") (pin "P5") (pinfunction "VIN_P5") (pintype "bidirectional"))
    )
    (net (code "48") (name "VCC_SENSE") (class "Default")
      (node (ref "R11") (pin "1") (pinfunction "1_1") (pintype "passive"))
      (node (ref "R12") (pin "2") (pinfunction "2_2") (pintype "passive"))
      (node (ref "U3") (pin "P6") (pinfunction "P1.5/TB0.2/UCACLK_P6") (pintype "bidirectional"))
    )
    (net (code "49") (name "VFILT") (class "Default")
      (node (ref "C39") (pin "2") (pinfunction "2_2") (pintype "passive"))
      (node (ref "R35") (pin "2") (pinfunction "2_2") (pintype "passive"))
      (node (ref "SV1") (pin "P9") (pinfunction "9_P9") (pintype "passive"))
      (node (ref "U3") (pin "P2") (pinfunction "P1.1/VREF+_P2") (pintype "bidirectional"))
      (node (ref "U7") (pin "P5") (pinfunction "IN+_P5") (pintype "bidirectional"))
    )
    (net (code "50") (name "VS+") (class "Default")
      (node (ref "C10") (pin "1") (pinfunction "1_1") (pintype "passive"))
      (node (ref "C4") (pin "1") (pinfunction "1_1") (pintype "passive"))
      (node (ref "C9") (pin "1") (pinfunction "1_1") (pintype "passive"))
      (node (ref "L1") (pin "1") (pinfunction "1_1") (pintype "passive"))
      (node (ref "R24") (pin "1") (pinfunction "1_1") (pintype "passive"))
      (node (ref "R7") (pin "2") (pinfunction "2_2") (pintype "passive"))
      (node (ref "SV1") (pin "P12") (pinfunction "12_P12") (pintype "passive"))
      (node (ref "U1") (pin "P2") (pinfunction "VOUT_P2") (pintype "bidirectional"))
    )
    (net (code "51") (name "VTEST") (class "Default")
      (node (ref "J2") (pin "PA.3") (pinfunction "P_PA.3") (pintype "bidirectional"))
      (node (ref "R3") (pin "1") (pinfunction "1_1") (pintype "passive"))
      (node (ref "RI1") (pin "1") (pinfunction "1_1") (pintype "passive"))
    )
    (net (code "52") (name "V_SENSE") (class "Default")
      (node (ref "RF") (pin "2") (pinfunction "2_2") (pintype "passive"))
      (node (ref "SV1") (pin "P3") (pinfunction "3_P3") (pintype "passive"))
      (node (ref "U3") (pin "P1") (pinfunction "P1.0/VREF-_P1") (pintype "bidirectional"))
      (node (ref "U6") (pin "P4") (pinfunction "OUT_P4") (pintype "bidirectional"))
    )
    (net (code "53") (name "ZC") (class "Default")
      (node (ref "D1") (pin "C") (pinfunction "C_C") (pintype "passive"))
      (node (ref "D2") (pin "A") (pinfunction "A_A") (pintype "passive"))
      (node (ref "R22") (pin "2") (pinfunction "2_2") (pintype "passive"))
      (node (ref "R3") (pin "2") (pinfunction "2_2") (pintype "passive"))
      (node (ref "SV1") (pin "P11") (pinfunction "11_P11") (pintype "passive"))
    )
    (net (code "54") (name "unconnected-(J1-4-PadP4)") (class "Default")
      (node (ref "J1") (pin "P4") (pinfunction "4_P4") (pintype "bidirectional"))
    )
    (net (code "55") (name "unconnected-(J1-6-PadP6)") (class "Default")
      (node (ref "J1") (pin "P6") (pinfunction "6_P6") (pintype "bidirectional"))
    )
    (net (code "56") (name "unconnected-(J4-SWO-Pad6)") (class "Default")
      (node (ref "J4") (pin "6") (pinfunction "SWO_6") (pintype "bidirectional"))
    )
    (net (code "57") (name "unconnected-(J4-~{RESET}-Pad3)") (class "Default")
      (node (ref "J4") (pin "3") (pinfunction "~{RESET}_3") (pintype "bidirectional"))
    )
    (net (code "58") (name "unconnected-(U4-P00{slash}AREF0-Pad4)") (class "Default")
      (node (ref "U4") (pin "4") (pinfunction "P00/AREF0_4") (pintype "bidirectional"))
    )
    (net (code "59") (name "unconnected-(U4-P01{slash}AIN2-Pad5)") (class "Default")
      (node (ref "U4") (pin "5") (pinfunction "P01/AIN2_5") (pintype "bidirectional"))
    )
    (net (code "60") (name "unconnected-(U4-P02{slash}AIN3-Pad6)") (class "Default")
      (node (ref "U4") (pin "6") (pinfunction "P02/AIN3_6") (pintype "bidirectional"))
    )
    (net (code "61") (name "unconnected-(U4-P03{slash}AIN4-Pad7)") (class "Default")
      (node (ref "U4") (pin "7") (pinfunction "P03/AIN4_7") (pintype "bidirectional"))
    )
    (net (code "62") (name "unconnected-(U4-P04{slash}AIN5-Pad8)") (class "Default")
      (node (ref "U4") (pin "8") (pinfunction "P04/AIN5_8") (pintype "bidirectional"))
    )
    (net (code "63") (name "unconnected-(U4-P06{slash}AIN7{slash}AREF1-Pad10)") (class "Default")
      (node (ref "U4") (pin "10") (pinfunction "P06/AIN7/AREF1_10") (pintype "bidirectional"))
    )
    (net (code "64") (name "unconnected-(U4-P07-Pad11)") (class "Default")
      (node (ref "U4") (pin "11") (pinfunction "P07_11") (pintype "bidirectional"))
    )
    (net (code "65") (name "unconnected-(U4-P08-Pad14)") (class "Default")
      (node (ref "U4") (pin "14") (pinfunction "P08_14") (pintype "bidirectional"))
    )
    (net (code "66") (name "unconnected-(U4-P09-Pad15)") (class "Default")
      (node (ref "U4") (pin "15") (pinfunction "P09_15") (pintype "bidirectional"))
    )
    (net (code "67") (name "unconnected-(U4-P10-Pad16)") (class "Default")
      (node (ref "U4") (pin "16") (pinfunction "P10_16") (pintype "bidirectional"))
    )
    (net (code "68") (name "unconnected-(U4-P11-Pad17)") (class "Default")
      (node (ref "U4") (pin "17") (pinfunction "P11_17") (pintype "bidirectional"))
    )
    (net (code "69") (name "unconnected-(U4-P12-Pad18)") (class "Default")
      (node (ref "U4") (pin "18") (pinfunction "P12_18") (pintype "bidirectional"))
    )
    (net (code "70") (name "unconnected-(U4-P13-Pad19)") (class "Default")
      (node (ref "U4") (pin "19") (pinfunction "P13_19") (pintype "bidirectional"))
    )
    (net (code "71") (name "unconnected-(U4-P14-Pad20)") (class "Default")
      (node (ref "U4") (pin "20") (pinfunction "P14_20") (pintype "bidirectional"))
    )
    (net (code "72") (name "unconnected-(U4-P15-Pad21)") (class "Default")
      (node (ref "U4") (pin "21") (pinfunction "P15_21") (pintype "bidirectional"))
    )
    (net (code "73") (name "unconnected-(U4-P16-Pad22)") (class "Default")
      (node (ref "U4") (pin "22") (pinfunction "P16_22") (pintype "bidirectional"))
    )
    (net (code "74") (name "unconnected-(U4-P17-Pad25)") (class "Default")
      (node (ref "U4") (pin "25") (pinfunction "P17_25") (pintype "bidirectional"))
    )
    (net (code "75") (name "unconnected-(U4-P18-Pad26)") (class "Default")
      (node (ref "U4") (pin "26") (pinfunction "P18_26") (pintype "bidirectional"))
    )
    (net (code "76") (name "unconnected-(U4-P19-Pad27)") (class "Default")
      (node (ref "U4") (pin "27") (pinfunction "P19_27") (pintype "bidirectional"))
    )
    (net (code "77") (name "unconnected-(U4-P20-Pad28)") (class "Default")
      (node (ref "U4") (pin "28") (pinfunction "P20_28") (pintype "bidirectional"))
    )
    (net (code "78") (name "unconnected-(U4-P21-Pad40)") (class "Default")
      (node (ref "U4") (pin "40") (pinfunction "P21_40") (pintype "bidirectional"))
    )
    (net (code "79") (name "unconnected-(U4-P22-Pad41)") (class "Default")
      (node (ref "U4") (pin "41") (pinfunction "P22_41") (pintype "bidirectional"))
    )
    (net (code "80") (name "unconnected-(U4-P23-Pad42)") (class "Default")
      (node (ref "U4") (pin "42") (pinfunction "P23_42") (pintype "bidirectional"))
    )
    (net (code "81") (name "unconnected-(U4-P24-Pad43)") (class "Default")
      (node (ref "U4") (pin "43") (pinfunction "P24_43") (pintype "bidirectional"))
    )
    (net (code "82") (name "unconnected-(U4-P25-Pad44)") (class "Default")
      (node (ref "U4") (pin "44") (pinfunction "P25_44") (pintype "bidirectional"))
    )
    (net (code "83") (name "unconnected-(U4-P26{slash}AIN0{slash}XL2-Pad45)") (class "Default")
      (node (ref "U4") (pin "45") (pinfunction "P26/AIN0/XL2_45") (pintype "bidirectional"))
    )
    (net (code "84") (name "unconnected-(U4-P30-Pad3)") (class "Default")
      (node (ref "U4") (pin "3") (pinfunction "P30_3") (pintype "bidirectional"))
    )
  )
)
